# CH32F203VCT6-R0.net
KiCad netlist of a schematic drawn in Altium Designer
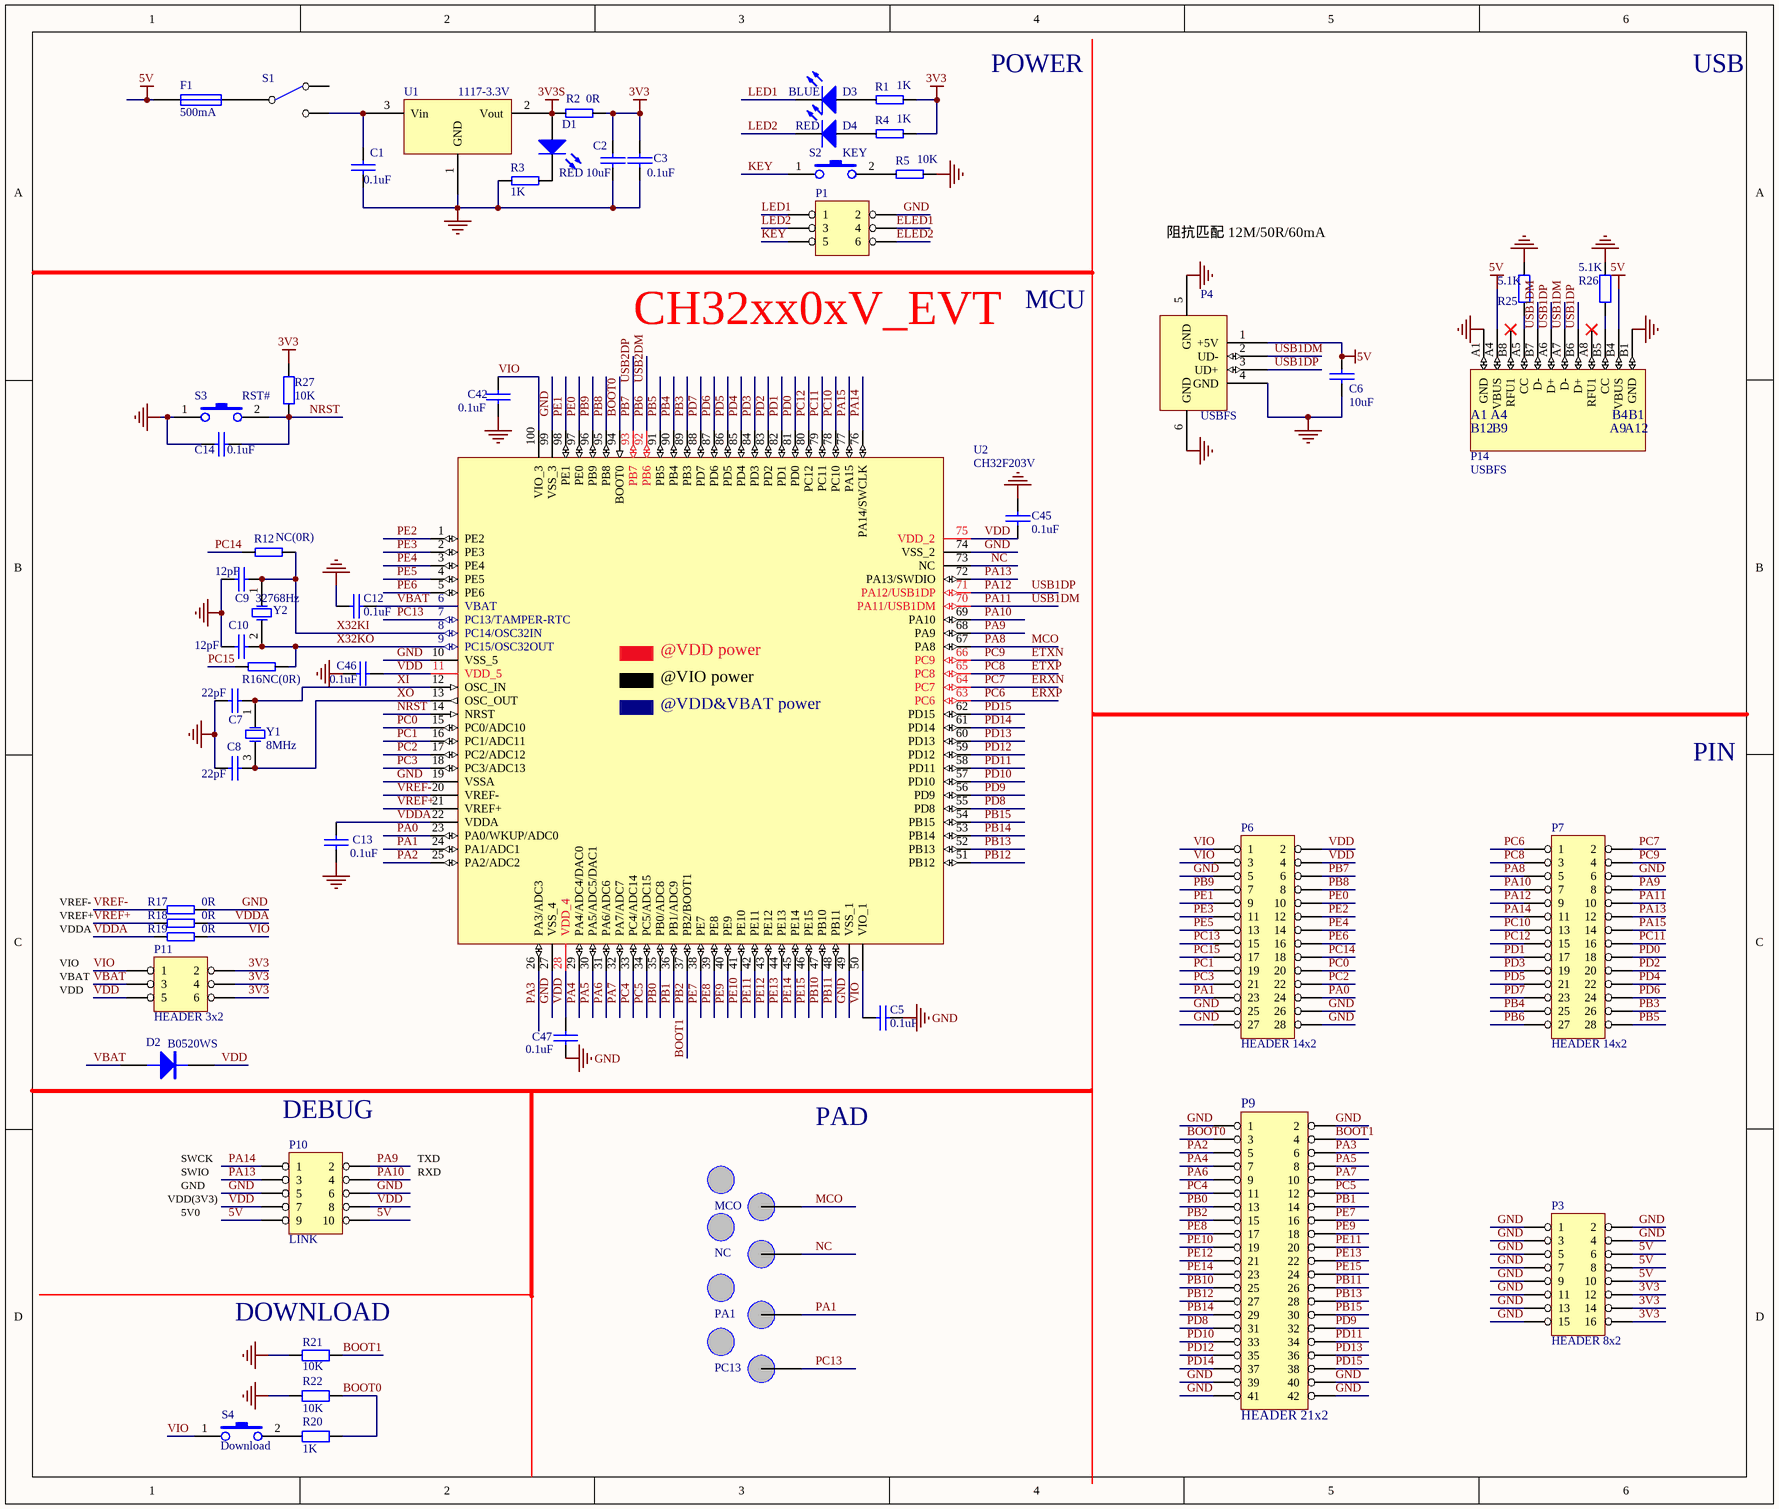
[diagram p0: CH32F203VCT6-R0.SchDoc]

(export (version "E")
  (design (tool "Eeschema 10.0.6"))
  (components
    (comp (ref "C1")
      (value "0.1uF")
      (footprint "0603_C")
      (description "Capacitor")
      (libsource (lib "*") (part "CAP"))
    )
    (comp (ref "C2")
      (value "10uF")
      (footprint "3216_C")
      (description "Capacitor")
      (libsource (lib "*") (part "CAP"))
    )
    (comp (ref "C3")
      (value "0.1uF")
      (footprint "0603_C")
      (description "Capacitor")
      (libsource (lib "*") (part "CAP"))
    )
    (comp (ref "C5")
      (value "0.1uF")
      (footprint "0603_C")
      (description "Capacitor")
      (libsource (lib "*") (part "CAP"))
    )
    (comp (ref "C6")
      (value "10uF")
      (footprint "3216_C")
      (description "Capacitor")
      (libsource (lib "") (part "CAP_1"))
    )
    (comp (ref "C7")
      (value "22pF")
      (footprint "0603_C")
      (description "Capacitor")
      (libsource (lib "*") (part "CAP"))
    )
    (comp (ref "C8")
      (value "22pF")
      (footprint "0603_C")
      (description "Capacitor")
      (libsource (lib "*") (part "CAP"))
    )
    (comp (ref "C9")
      (value "12pF")
      (footprint "0603_C")
      (description "Capacitor")
      (libsource (lib "*") (part "CAP"))
    )
    (comp (ref "C10")
      (value "12pF")
      (footprint "0603_C")
      (description "Capacitor")
      (libsource (lib "*") (part "CAP"))
    )
    (comp (ref "C12")
      (value "0.1uF")
      (footprint "0603_C")
      (description "Capacitor")
      (libsource (lib "*") (part "CAP"))
    )
    (comp (ref "C13")
      (value "0.1uF")
      (footprint "0603_C")
      (description "Capacitor")
      (libsource (lib "*") (part "CAP"))
    )
    (comp (ref "C14")
      (value "0.1uF")
      (footprint "0603_C")
      (description "Capacitor")
      (libsource (lib "") (part "CAP_1"))
    )
    (comp (ref "C42")
      (value "0.1uF")
      (footprint "0603_C")
      (description "Capacitor")
      (libsource (lib "*") (part "CAP"))
    )
    (comp (ref "C45")
      (value "0.1uF")
      (footprint "0603_C")
      (description "Capacitor")
      (libsource (lib "*") (part "CAP"))
    )
    (comp (ref "C46")
      (value "0.1uF")
      (footprint "0603_C")
      (description "Capacitor")
      (libsource (lib "*") (part "CAP"))
    )
    (comp (ref "C47")
      (value "0.1uF")
      (footprint "0603_C")
      (description "Capacitor")
      (libsource (lib "*") (part "CAP"))
    )
    (comp (ref "D1")
      (value "RED")
      (footprint "0603+")
      (description "Typical INFRARED GaAs LED")
      (fields (field (name "PUBLISHER") "Altium Limited"))
      (libsource (lib "*") (part "LED0"))
    )
    (comp (ref "D2")
      (value "B0520WS")
      (footprint "SOD-323")
      (description "Diode")
      (libsource (lib "*") (part "DIODE"))
    )
    (comp (ref "D3")
      (value "BLUE")
      (footprint "0603+")
      (description "Typical INFRARED GaAs LED")
      (fields (field (name "PUBLISHER") "Altium Limited"))
      (libsource (lib "*") (part "LED0"))
    )
    (comp (ref "D4")
      (value "RED")
      (footprint "0603+")
      (description "Typical INFRARED GaAs LED")
      (fields (field (name "PUBLISHER") "Altium Limited"))
      (libsource (lib "*") (part "LED0"))
    )
    (comp (ref "F1")
      (value "500mA")
      (footprint "0805")
      (description "Fuse")
      (libsource (lib "wch_sch_others") (part "FUSE1"))
    )
    (comp (ref "MCO")
      (value "Testpoint")
      (footprint "TESTPOINT1")
      (description "测试点")
      (libsource (lib "wch_sch_others") (part "Testpoint"))
    )
    (comp (ref "NC")
      (value "Testpoint")
      (footprint "TESTPOINT1")
      (description "测试点")
      (libsource (lib "wch_sch_others") (part "Testpoint"))
    )
    (comp (ref "P1")
      (value "IO")
      (footprint "MYPCB:IDC6-2.54mm")
      (description "Header, 3-Pin, Dual row")
      (libsource (lib "wch_sch_others") (part "HEADER 3x2"))
    )
    (comp (ref "P3")
      (value "HEADER 8x2")
      (footprint "MYPCB:IDC16-2.54mm")
      (description "Header, 8-Pin, Dual row")
      (libsource (lib "wch_sch_others") (part "HEADER 8x2"))
    )
    (comp (ref "P4")
      (value "USBFS")
      (footprint "USBAF")
      (description "USB Port")
      (libsource (lib "*") (part "USB"))
    )
    (comp (ref "P6")
      (value "HEADER 14x2")
      (footprint "MYPCB:IDC28-2.54MM")
      (description "Header, 14-Pin, Dual row")
      (libsource (lib "wch_sch_others") (part "HEADER 14x2"))
    )
    (comp (ref "P7")
      (value "HEADER 14x2")
      (footprint "MYPCB:IDC28-2.54MM")
      (description "Header, 14-Pin, Dual row")
      (libsource (lib "wch_sch_others") (part "HEADER 14x2"))
    )
    (comp (ref "P9")
      (value "HEADER 21x2")
      (footprint "MYPCB:IDC42-2.54MM")
      (description "Header, 21-Pin, Dual row")
      (libsource (lib "wch_sch_others") (part "HEADER 21x2"))
    )
    (comp (ref "P10")
      (value "LINK")
      (footprint "MYPCB:IDC10-2.54mm")
      (description "Header, 5-Pin, Dual row")
      (libsource (lib "wch_sch_others") (part "HEADER 5x2"))
    )
    (comp (ref "P11")
      (value "HEADER 3x2")
      (footprint "MYPCB:IDC6-2.54mm")
      (description "Header, 3-Pin, Dual row")
      (libsource (lib "wch_sch_others") (part "HEADER 3x2"))
    )
    (comp (ref "P14")
      (value "USBFS")
      (footprint "TYPE-C-Receptacle-2.0")
      (libsource (lib "*") (part "TYPE-C1"))
    )
    (comp (ref "PA1")
      (value "Testpoint")
      (footprint "TESTPOINT1")
      (description "测试点")
      (libsource (lib "wch_sch_others") (part "Testpoint"))
    )
    (comp (ref "PC13")
      (value "Testpoint")
      (footprint "TESTPOINT1")
      (description "测试点")
      (libsource (lib "wch_sch_others") (part "Testpoint"))
    )
    (comp (ref "R1") (value "1K") (footprint "0603") (libsource (lib "wch_sch_others") (part "RES")))
    (comp (ref "R2") (value "0R") (footprint "0603") (libsource (lib "wch_sch_others") (part "RES")))
    (comp (ref "R3") (value "1K") (footprint "0603") (libsource (lib "wch_sch_others") (part "RES")))
    (comp (ref "R4") (value "1K") (footprint "0603") (libsource (lib "wch_sch_others") (part "RES")))
    (comp (ref "R5") (value "10K") (footprint "0603") (libsource (lib "wch_sch_others") (part "RES")))
    (comp (ref "R12") (value "NC(0R)") (footprint "0603") (libsource (lib "wch_sch_others") (part "RES")))
    (comp (ref "R16") (value "NC(0R)") (footprint "0603") (libsource (lib "wch_sch_others") (part "RES")))
    (comp (ref "R17") (value "0R") (footprint "0603") (libsource (lib "*") (part "R")))
    (comp (ref "R18") (value "0R") (footprint "0603") (libsource (lib "*") (part "R")))
    (comp (ref "R19") (value "0R") (footprint "0603") (libsource (lib "*") (part "R")))
    (comp (ref "R20")
      (value "1K")
      (footprint "0603")
      (description "Resistor")
      (fields (field (name "PUBLISHER") "Altium Limited"))
      (libsource (lib "Miscellaneous Devices") (part "Res2"))
    )
    (comp (ref "R21")
      (value "10K")
      (footprint "0603")
      (description "Resistor")
      (fields (field (name "PUBLISHER") "Altium Limited"))
      (libsource (lib "Miscellaneous Devices") (part "Res2"))
    )
    (comp (ref "R22")
      (value "10K")
      (footprint "0603")
      (description "Resistor")
      (fields (field (name "PUBLISHER") "Altium Limited"))
      (libsource (lib "Miscellaneous Devices") (part "Res2"))
    )
    (comp (ref "R25")
      (value "5.1K")
      (footprint "0603")
      (description "Resistor")
      (libsource (lib "") (part "Res2_1"))
    )
    (comp (ref "R26")
      (value "5.1K")
      (footprint "0603")
      (description "Resistor")
      (libsource (lib "") (part "Res2_1"))
    )
    (comp (ref "R27")
      (value "10K")
      (footprint "0603")
      (description "Resistor")
      (fields (field (name "PUBLISHER") "Altium Limited"))
      (libsource (lib "") (part "Res2_1"))
    )
    (comp (ref "S1") (value "SW SPDT") (footprint "KEY2") (libsource (lib "*") (part "SW SPDT")))
    (comp (ref "S2")
      (value "KEY")
      (footprint "SMD_6.1x3.65x2.5mm-KEY")
      (libsource (lib "wch_sch_others") (part "KEY1"))
    )
    (comp (ref "S3")
      (value "RST#")
      (footprint "SMD_6.1x3.65x2.5mm-KEY")
      (libsource (lib "wch_sch_others") (part "KEY1"))
    )
    (comp (ref "S4")
      (value "Download")
      (footprint "SMD_6.1x3.65x2.5mm-KEY")
      (libsource (lib "wch_sch_others") (part "KEY1"))
    )
    (comp (ref "U1")
      (value "1117-3.3V")
      (footprint "SOT-223")
      (libsource (lib "wch_sch_others") (part "1117-3.3V"))
    )
    (comp (ref "U2")
      (value "CH32F203V")
      (footprint "LQFP100")
      (description "ARM M3 HD-MCU, 144MHz, 8*UART, 10*Timer, 4*OPA")
      (libsource (lib "CHXXX") (part "CH32F203V"))
    )
    (comp (ref "Y1")
      (value "8MHz")
      (footprint "XT3225")
      (description "Crystal Oscillator")
      (fields (field (name "PUBLISHER") "Altium Limited"))
      (libsource (lib "*") (part "XTAL"))
    )
    (comp (ref "Y2")
      (value "32768Hz")
      (footprint "FC-135")
      (description "Crystal Oscillator")
      (fields (field (name "PUBLISHER") "Altium Limited"))
      (libsource (lib "") (part "XTAL_1"))
    )
  )
  (nets
    (net (code "2") (name "/BOOT0") (class "Default")
      (node (ref "P9") (pin "3") (pinfunction "3_3") (pintype "passive"))
      (node (ref "R20") (pin "1") (pinfunction "1_1") (pintype "passive"))
      (node (ref "R22") (pin "1") (pinfunction "1_1") (pintype "passive"))
      (node (ref "U2") (pin "94") (pinfunction "BOOT0_94") (pintype "input"))
    )
    (net (code "3") (name "/BOOT1") (class "Default")
      (node (ref "P9") (pin "15") (pinfunction "15_15") (pintype "passive"))
      (node (ref "P9") (pin "4") (pinfunction "4_4") (pintype "passive"))
      (node (ref "R21") (pin "1") (pinfunction "1_1") (pintype "passive"))
      (node (ref "U2") (pin "37") (pinfunction "PB2/BOOT1_37") (pintype "bidirectional"))
    )
    (net (code "4") (name "/ELED1") (class "Default")
      (node (ref "P1") (pin "4") (pinfunction "4_4") (pintype "passive"))
    )
    (net (code "5") (name "/ELED2") (class "Default")
      (node (ref "P1") (pin "6") (pinfunction "6_6") (pintype "passive"))
    )
    (net (code "6") (name "/ERXN") (class "Default")
      (node (ref "P7") (pin "2") (pinfunction "2_2") (pintype "passive"))
      (node (ref "U2") (pin "64") (pinfunction "PC7_64") (pintype "bidirectional"))
    )
    (net (code "7") (name "/ERXP") (class "Default")
      (node (ref "P7") (pin "1") (pinfunction "1_1") (pintype "passive"))
      (node (ref "U2") (pin "63") (pinfunction "PC6_63") (pintype "bidirectional"))
    )
    (net (code "8") (name "/ETXN") (class "Default")
      (node (ref "P7") (pin "4") (pinfunction "4_4") (pintype "passive"))
      (node (ref "U2") (pin "66") (pinfunction "PC9_66") (pintype "bidirectional"))
    )
    (net (code "9") (name "/ETXP") (class "Default")
      (node (ref "P7") (pin "3") (pinfunction "3_3") (pintype "passive"))
      (node (ref "U2") (pin "65") (pinfunction "PC8_65") (pintype "bidirectional"))
    )
    (net (code "10") (name "/KEY") (class "Default")
      (node (ref "P1") (pin "5") (pinfunction "5_5") (pintype "passive"))
      (node (ref "S2") (pin "1") (pinfunction "1_1") (pintype "passive"))
    )
    (net (code "11") (name "/LED1") (class "Default")
      (node (ref "D3") (pin "2") (pinfunction "K_2") (pintype "passive"))
      (node (ref "P1") (pin "1") (pinfunction "1_1") (pintype "passive"))
    )
    (net (code "12") (name "/LED2") (class "Default")
      (node (ref "D4") (pin "2") (pinfunction "K_2") (pintype "passive"))
      (node (ref "P1") (pin "3") (pinfunction "3_3") (pintype "passive"))
    )
    (net (code "13") (name "/MCO") (class "Default")
      (node (ref "MCO") (pin "1") (pinfunction "point_1") (pintype "passive"))
      (node (ref "P7") (pin "5") (pinfunction "5_5") (pintype "passive"))
      (node (ref "U2") (pin "67") (pinfunction "PA8_67") (pintype "bidirectional"))
    )
    (net (code "14") (name "/NC") (class "Default")
      (node (ref "NC") (pin "1") (pinfunction "point_1") (pintype "passive"))
      (node (ref "U2") (pin "73") (pinfunction "NC_73") (pintype "tri_state"))
    )
    (net (code "15") (name "/NRST") (class "Default")
      (node (ref "C14") (pin "2") (pinfunction "2_2") (pintype "passive"))
      (node (ref "R27") (pin "1") (pinfunction "1_1") (pintype "passive"))
      (node (ref "S3") (pin "2") (pinfunction "2_2") (pintype "passive"))
      (node (ref "U2") (pin "14") (pinfunction "NRST_14") (pintype "input"))
    )
    (net (code "16") (name "/PA0") (class "Default")
      (node (ref "P6") (pin "24") (pinfunction "24_24") (pintype "passive"))
      (node (ref "U2") (pin "23") (pinfunction "PA0/WKUP/ADC0_23") (pintype "bidirectional"))
    )
    (net (code "17") (name "/PA1") (class "Default")
      (node (ref "P6") (pin "23") (pinfunction "23_23") (pintype "passive"))
      (node (ref "PA1") (pin "1") (pinfunction "point_1") (pintype "passive"))
      (node (ref "U2") (pin "24") (pinfunction "PA1/ADC1_24") (pintype "bidirectional"))
    )
    (net (code "18") (name "/PA2") (class "Default")
      (node (ref "P9") (pin "5") (pinfunction "5_5") (pintype "passive"))
      (node (ref "U2") (pin "25") (pinfunction "PA2/ADC2_25") (pintype "bidirectional"))
    )
    (net (code "19") (name "/PA3") (class "Default")
      (node (ref "P9") (pin "6") (pinfunction "6_6") (pintype "passive"))
      (node (ref "U2") (pin "26") (pinfunction "PA3/ADC3_26") (pintype "bidirectional"))
    )
    (net (code "20") (name "/PA4") (class "Default")
      (node (ref "P9") (pin "7") (pinfunction "7_7") (pintype "passive"))
      (node (ref "U2") (pin "29") (pinfunction "PA4/ADC4/DAC0_29") (pintype "bidirectional"))
    )
    (net (code "21") (name "/PA5") (class "Default")
      (node (ref "P9") (pin "8") (pinfunction "8_8") (pintype "passive"))
      (node (ref "U2") (pin "30") (pinfunction "PA5/ADC5/DAC1_30") (pintype "bidirectional"))
    )
    (net (code "22") (name "/PA6") (class "Default")
      (node (ref "P9") (pin "9") (pinfunction "9_9") (pintype "passive"))
      (node (ref "U2") (pin "31") (pinfunction "PA6/ADC6_31") (pintype "bidirectional"))
    )
    (net (code "23") (name "/PA7") (class "Default")
      (node (ref "P9") (pin "10") (pinfunction "10_10") (pintype "passive"))
      (node (ref "U2") (pin "32") (pinfunction "PA7/ADC7_32") (pintype "bidirectional"))
    )
    (net (code "24") (name "/PA9") (class "Default")
      (node (ref "P10") (pin "2") (pinfunction "2_2") (pintype "passive"))
      (node (ref "P7") (pin "8") (pinfunction "8_8") (pintype "passive"))
      (node (ref "U2") (pin "68") (pinfunction "PA9_68") (pintype "bidirectional"))
    )
    (net (code "25") (name "/PA10") (class "Default")
      (node (ref "P10") (pin "4") (pinfunction "4_4") (pintype "passive"))
      (node (ref "P7") (pin "7") (pinfunction "7_7") (pintype "passive"))
      (node (ref "U2") (pin "69") (pinfunction "PA10_69") (pintype "bidirectional"))
    )
    (net (code "26") (name "/PA11") (class "Default")
      (node (ref "P14") (pin "A7") (pinfunction "D-_A7") (pintype "bidirectional"))
      (node (ref "P14") (pin "B7") (pinfunction "D-_B7") (pintype "bidirectional"))
      (node (ref "P4") (pin "2") (pinfunction "UD-_2") (pintype "bidirectional"))
      (node (ref "P7") (pin "10") (pinfunction "10_10") (pintype "passive"))
      (node (ref "U2") (pin "70") (pinfunction "PA11/USB1DM_70") (pintype "bidirectional"))
    )
    (net (code "27") (name "/PA12") (class "Default")
      (node (ref "P14") (pin "A6") (pinfunction "D+_A6") (pintype "bidirectional"))
      (node (ref "P14") (pin "B6") (pinfunction "D+_B6") (pintype "bidirectional"))
      (node (ref "P4") (pin "3") (pinfunction "UD+_3") (pintype "bidirectional"))
      (node (ref "P7") (pin "9") (pinfunction "9_9") (pintype "passive"))
      (node (ref "U2") (pin "71") (pinfunction "PA12/USB1DP_71") (pintype "bidirectional"))
    )
    (net (code "28") (name "/PA13") (class "Default")
      (node (ref "P10") (pin "3") (pinfunction "3_3") (pintype "passive"))
      (node (ref "P7") (pin "12") (pinfunction "12_12") (pintype "passive"))
      (node (ref "U2") (pin "72") (pinfunction "PA13/SWDIO_72") (pintype "bidirectional"))
    )
    (net (code "29") (name "/PA14") (class "Default")
      (node (ref "P10") (pin "1") (pinfunction "1_1") (pintype "passive"))
      (node (ref "P7") (pin "11") (pinfunction "11_11") (pintype "passive"))
      (node (ref "U2") (pin "76") (pinfunction "PA14/SWCLK_76") (pintype "bidirectional"))
    )
    (net (code "30") (name "/PA15") (class "Default")
      (node (ref "P7") (pin "14") (pinfunction "14_14") (pintype "passive"))
      (node (ref "U2") (pin "77") (pinfunction "PA15_77") (pintype "bidirectional"))
    )
    (net (code "31") (name "/PB0") (class "Default")
      (node (ref "P9") (pin "13") (pinfunction "13_13") (pintype "passive"))
      (node (ref "U2") (pin "35") (pinfunction "PB0/ADC8_35") (pintype "bidirectional"))
    )
    (net (code "32") (name "/PB1") (class "Default")
      (node (ref "P9") (pin "14") (pinfunction "14_14") (pintype "passive"))
      (node (ref "U2") (pin "36") (pinfunction "PB1/ADC9_36") (pintype "bidirectional"))
    )
    (net (code "33") (name "/PB3") (class "Default")
      (node (ref "P7") (pin "26") (pinfunction "26_26") (pintype "passive"))
      (node (ref "U2") (pin "89") (pinfunction "PB3_89") (pintype "bidirectional"))
    )
    (net (code "34") (name "/PB4") (class "Default")
      (node (ref "P7") (pin "25") (pinfunction "25_25") (pintype "passive"))
      (node (ref "U2") (pin "90") (pinfunction "PB4_90") (pintype "bidirectional"))
    )
    (net (code "35") (name "/PB5") (class "Default")
      (node (ref "P7") (pin "28") (pinfunction "28_28") (pintype "passive"))
      (node (ref "U2") (pin "91") (pinfunction "PB5_91") (pintype "bidirectional"))
    )
    (net (code "36") (name "/PB6") (class "Default")
      (node (ref "P7") (pin "27") (pinfunction "27_27") (pintype "passive"))
      (node (ref "U2") (pin "92") (pinfunction "PB6_92") (pintype "bidirectional"))
    )
    (net (code "37") (name "/PB7") (class "Default")
      (node (ref "P6") (pin "6") (pinfunction "6_6") (pintype "passive"))
      (node (ref "U2") (pin "93") (pinfunction "PB7_93") (pintype "bidirectional"))
    )
    (net (code "38") (name "/PB8") (class "Default")
      (node (ref "P6") (pin "8") (pinfunction "8_8") (pintype "passive"))
      (node (ref "U2") (pin "95") (pinfunction "PB8_95") (pintype "bidirectional"))
    )
    (net (code "39") (name "/PB9") (class "Default")
      (node (ref "P6") (pin "7") (pinfunction "7_7") (pintype "passive"))
      (node (ref "U2") (pin "96") (pinfunction "PB9_96") (pintype "bidirectional"))
    )
    (net (code "40") (name "/PB10") (class "Default")
      (node (ref "P9") (pin "25") (pinfunction "25_25") (pintype "passive"))
      (node (ref "U2") (pin "47") (pinfunction "PB10_47") (pintype "bidirectional"))
    )
    (net (code "41") (name "/PB11") (class "Default")
      (node (ref "P9") (pin "26") (pinfunction "26_26") (pintype "passive"))
      (node (ref "U2") (pin "48") (pinfunction "PB11_48") (pintype "bidirectional"))
    )
    (net (code "42") (name "/PB12") (class "Default")
      (node (ref "P9") (pin "27") (pinfunction "27_27") (pintype "passive"))
      (node (ref "U2") (pin "51") (pinfunction "PB12_51") (pintype "bidirectional"))
    )
    (net (code "43") (name "/PB13") (class "Default")
      (node (ref "P9") (pin "28") (pinfunction "28_28") (pintype "passive"))
      (node (ref "U2") (pin "52") (pinfunction "PB13_52") (pintype "bidirectional"))
    )
    (net (code "44") (name "/PB14") (class "Default")
      (node (ref "P9") (pin "29") (pinfunction "29_29") (pintype "passive"))
      (node (ref "U2") (pin "53") (pinfunction "PB14_53") (pintype "bidirectional"))
    )
    (net (code "45") (name "/PB15") (class "Default")
      (node (ref "P9") (pin "30") (pinfunction "30_30") (pintype "passive"))
      (node (ref "U2") (pin "54") (pinfunction "PB15_54") (pintype "bidirectional"))
    )
    (net (code "46") (name "/PC0") (class "Default")
      (node (ref "P6") (pin "20") (pinfunction "20_20") (pintype "passive"))
      (node (ref "U2") (pin "15") (pinfunction "PC0/ADC10_15") (pintype "bidirectional"))
    )
    (net (code "47") (name "/PC1") (class "Default")
      (node (ref "P6") (pin "19") (pinfunction "19_19") (pintype "passive"))
      (node (ref "U2") (pin "16") (pinfunction "PC1/ADC11_16") (pintype "bidirectional"))
    )
    (net (code "48") (name "/PC2") (class "Default")
      (node (ref "P6") (pin "22") (pinfunction "22_22") (pintype "passive"))
      (node (ref "U2") (pin "17") (pinfunction "PC2/ADC12_17") (pintype "bidirectional"))
    )
    (net (code "49") (name "/PC3") (class "Default")
      (node (ref "P6") (pin "21") (pinfunction "21_21") (pintype "passive"))
      (node (ref "U2") (pin "18") (pinfunction "PC3/ADC13_18") (pintype "bidirectional"))
    )
    (net (code "50") (name "/PC4") (class "Default")
      (node (ref "P9") (pin "11") (pinfunction "11_11") (pintype "passive"))
      (node (ref "U2") (pin "33") (pinfunction "PC4/ADC14_33") (pintype "bidirectional"))
    )
    (net (code "51") (name "/PC5") (class "Default")
      (node (ref "P9") (pin "12") (pinfunction "12_12") (pintype "passive"))
      (node (ref "U2") (pin "34") (pinfunction "PC5/ADC15_34") (pintype "bidirectional"))
    )
    (net (code "52") (name "/PC10") (class "Default")
      (node (ref "P7") (pin "13") (pinfunction "13_13") (pintype "passive"))
      (node (ref "U2") (pin "78") (pinfunction "PC10_78") (pintype "bidirectional"))
    )
    (net (code "53") (name "/PC11") (class "Default")
      (node (ref "P7") (pin "16") (pinfunction "16_16") (pintype "passive"))
      (node (ref "U2") (pin "79") (pinfunction "PC11_79") (pintype "bidirectional"))
    )
    (net (code "54") (name "/PC12") (class "Default")
      (node (ref "P7") (pin "15") (pinfunction "15_15") (pintype "passive"))
      (node (ref "U2") (pin "80") (pinfunction "PC12_80") (pintype "bidirectional"))
    )
    (net (code "55") (name "/PC13") (class "Default")
      (node (ref "P6") (pin "15") (pinfunction "15_15") (pintype "passive"))
      (node (ref "PC13") (pin "1") (pinfunction "point_1") (pintype "passive"))
      (node (ref "U2") (pin "7") (pinfunction "PC13/TAMPER-RTC_7") (pintype "bidirectional"))
    )
    (net (code "56") (name "/PC14") (class "Default")
      (node (ref "P6") (pin "18") (pinfunction "18_18") (pintype "passive"))
      (node (ref "R12") (pin "1") (pintype "passive"))
    )
    (net (code "57") (name "/PC15") (class "Default")
      (node (ref "P6") (pin "17") (pinfunction "17_17") (pintype "passive"))
      (node (ref "R16") (pin "1") (pintype "passive"))
    )
    (net (code "58") (name "/PD0") (class "Default")
      (node (ref "P7") (pin "18") (pinfunction "18_18") (pintype "passive"))
      (node (ref "U2") (pin "81") (pinfunction "PD0_81") (pintype "bidirectional"))
    )
    (net (code "59") (name "/PD1") (class "Default")
      (node (ref "P7") (pin "17") (pinfunction "17_17") (pintype "passive"))
      (node (ref "U2") (pin "82") (pinfunction "PD1_82") (pintype "bidirectional"))
    )
    (net (code "60") (name "/PD2") (class "Default")
      (node (ref "P7") (pin "20") (pinfunction "20_20") (pintype "passive"))
      (node (ref "U2") (pin "83") (pinfunction "PD2_83") (pintype "bidirectional"))
    )
    (net (code "61") (name "/PD3") (class "Default")
      (node (ref "P7") (pin "19") (pinfunction "19_19") (pintype "passive"))
      (node (ref "U2") (pin "84") (pinfunction "PD3_84") (pintype "bidirectional"))
    )
    (net (code "62") (name "/PD4") (class "Default")
      (node (ref "P7") (pin "22") (pinfunction "22_22") (pintype "passive"))
      (node (ref "U2") (pin "85") (pinfunction "PD4_85") (pintype "bidirectional"))
    )
    (net (code "63") (name "/PD5") (class "Default")
      (node (ref "P7") (pin "21") (pinfunction "21_21") (pintype "passive"))
      (node (ref "U2") (pin "86") (pinfunction "PD5_86") (pintype "bidirectional"))
    )
    (net (code "64") (name "/PD6") (class "Default")
      (node (ref "P7") (pin "24") (pinfunction "24_24") (pintype "passive"))
      (node (ref "U2") (pin "87") (pinfunction "PD6_87") (pintype "bidirectional"))
    )
    (net (code "65") (name "/PD7") (class "Default")
      (node (ref "P7") (pin "23") (pinfunction "23_23") (pintype "passive"))
      (node (ref "U2") (pin "88") (pinfunction "PD7_88") (pintype "bidirectional"))
    )
    (net (code "66") (name "/PD8") (class "Default")
      (node (ref "P9") (pin "31") (pinfunction "31_31") (pintype "passive"))
      (node (ref "U2") (pin "55") (pinfunction "PD8_55") (pintype "bidirectional"))
    )
    (net (code "67") (name "/PD9") (class "Default")
      (node (ref "P9") (pin "32") (pinfunction "32_32") (pintype "passive"))
      (node (ref "U2") (pin "56") (pinfunction "PD9_56") (pintype "bidirectional"))
    )
    (net (code "68") (name "/PD10") (class "Default")
      (node (ref "P9") (pin "33") (pinfunction "33_33") (pintype "passive"))
      (node (ref "U2") (pin "57") (pinfunction "PD10_57") (pintype "bidirectional"))
    )
    (net (code "69") (name "/PD11") (class "Default")
      (node (ref "P9") (pin "34") (pinfunction "34_34") (pintype "passive"))
      (node (ref "U2") (pin "58") (pinfunction "PD11_58") (pintype "bidirectional"))
    )
    (net (code "70") (name "/PD12") (class "Default")
      (node (ref "P9") (pin "35") (pinfunction "35_35") (pintype "passive"))
      (node (ref "U2") (pin "59") (pinfunction "PD12_59") (pintype "bidirectional"))
    )
    (net (code "71") (name "/PD13") (class "Default")
      (node (ref "P9") (pin "36") (pinfunction "36_36") (pintype "passive"))
      (node (ref "U2") (pin "60") (pinfunction "PD13_60") (pintype "bidirectional"))
    )
    (net (code "72") (name "/PD14") (class "Default")
      (node (ref "P9") (pin "37") (pinfunction "37_37") (pintype "passive"))
      (node (ref "U2") (pin "61") (pinfunction "PD14_61") (pintype "bidirectional"))
    )
    (net (code "73") (name "/PD15") (class "Default")
      (node (ref "P9") (pin "38") (pinfunction "38_38") (pintype "passive"))
      (node (ref "U2") (pin "62") (pinfunction "PD15_62") (pintype "bidirectional"))
    )
    (net (code "74") (name "/PE0") (class "Default")
      (node (ref "P6") (pin "10") (pinfunction "10_10") (pintype "passive"))
      (node (ref "U2") (pin "97") (pinfunction "PE0_97") (pintype "bidirectional"))
    )
    (net (code "75") (name "/PE1") (class "Default")
      (node (ref "P6") (pin "9") (pinfunction "9_9") (pintype "passive"))
      (node (ref "U2") (pin "98") (pinfunction "PE1_98") (pintype "bidirectional"))
    )
    (net (code "76") (name "/PE2") (class "Default")
      (node (ref "P6") (pin "12") (pinfunction "12_12") (pintype "passive"))
      (node (ref "U2") (pin "1") (pinfunction "PE2_1") (pintype "bidirectional"))
    )
    (net (code "77") (name "/PE3") (class "Default")
      (node (ref "P6") (pin "11") (pinfunction "11_11") (pintype "passive"))
      (node (ref "U2") (pin "2") (pinfunction "PE3_2") (pintype "bidirectional"))
    )
    (net (code "78") (name "/PE4") (class "Default")
      (node (ref "P6") (pin "14") (pinfunction "14_14") (pintype "passive"))
      (node (ref "U2") (pin "3") (pinfunction "PE4_3") (pintype "bidirectional"))
    )
    (net (code "79") (name "/PE5") (class "Default")
      (node (ref "P6") (pin "13") (pinfunction "13_13") (pintype "passive"))
      (node (ref "U2") (pin "4") (pinfunction "PE5_4") (pintype "bidirectional"))
    )
    (net (code "80") (name "/PE6") (class "Default")
      (node (ref "P6") (pin "16") (pinfunction "16_16") (pintype "passive"))
      (node (ref "U2") (pin "5") (pinfunction "PE6_5") (pintype "bidirectional"))
    )
    (net (code "81") (name "/PE7") (class "Default")
      (node (ref "P9") (pin "16") (pinfunction "16_16") (pintype "passive"))
      (node (ref "U2") (pin "38") (pinfunction "PE7_38") (pintype "bidirectional"))
    )
    (net (code "82") (name "/PE8") (class "Default")
      (node (ref "P9") (pin "17") (pinfunction "17_17") (pintype "passive"))
      (node (ref "U2") (pin "39") (pinfunction "PE8_39") (pintype "bidirectional"))
    )
    (net (code "83") (name "/PE9") (class "Default")
      (node (ref "P9") (pin "18") (pinfunction "18_18") (pintype "passive"))
      (node (ref "U2") (pin "40") (pinfunction "PE9_40") (pintype "bidirectional"))
    )
    (net (code "84") (name "/PE10") (class "Default")
      (node (ref "P9") (pin "19") (pinfunction "19_19") (pintype "passive"))
      (node (ref "U2") (pin "41") (pinfunction "PE10_41") (pintype "bidirectional"))
    )
    (net (code "85") (name "/PE11") (class "Default")
      (node (ref "P9") (pin "20") (pinfunction "20_20") (pintype "passive"))
      (node (ref "U2") (pin "42") (pinfunction "PE11_42") (pintype "bidirectional"))
    )
    (net (code "86") (name "/PE12") (class "Default")
      (node (ref "P9") (pin "21") (pinfunction "21_21") (pintype "passive"))
      (node (ref "U2") (pin "43") (pinfunction "PE12_43") (pintype "bidirectional"))
    )
    (net (code "87") (name "/PE13") (class "Default")
      (node (ref "P9") (pin "22") (pinfunction "22_22") (pintype "passive"))
      (node (ref "U2") (pin "44") (pinfunction "PE13_44") (pintype "bidirectional"))
    )
    (net (code "88") (name "/PE14") (class "Default")
      (node (ref "P9") (pin "23") (pinfunction "23_23") (pintype "passive"))
      (node (ref "U2") (pin "45") (pinfunction "PE14_45") (pintype "bidirectional"))
    )
    (net (code "89") (name "/PE15") (class "Default")
      (node (ref "P9") (pin "24") (pinfunction "24_24") (pintype "passive"))
      (node (ref "U2") (pin "46") (pinfunction "PE15_46") (pintype "bidirectional"))
    )
    (net (code "90") (name "/VBAT") (class "Default")
      (node (ref "C12") (pin "2") (pinfunction "2_2") (pintype "passive"))
      (node (ref "D2") (pin "1") (pinfunction "A_1") (pintype "passive"))
      (node (ref "P11") (pin "3") (pinfunction "3_3") (pintype "passive"))
      (node (ref "U2") (pin "6") (pinfunction "VBAT_6") (pintype "power_in"))
    )
    (net (code "91") (name "/VDD") (class "Default")
      (node (ref "C45") (pin "1") (pinfunction "1_1") (pintype "passive"))
      (node (ref "C46") (pin "1") (pinfunction "1_1") (pintype "passive"))
      (node (ref "C47") (pin "2") (pinfunction "2_2") (pintype "passive"))
      (node (ref "D2") (pin "2") (pinfunction "K_2") (pintype "passive"))
      (node (ref "P10") (pin "7") (pinfunction "7_7") (pintype "passive"))
      (node (ref "P10") (pin "8") (pinfunction "8_8") (pintype "passive"))
      (node (ref "P11") (pin "5") (pinfunction "5_5") (pintype "passive"))
      (node (ref "P6") (pin "2") (pinfunction "2_2") (pintype "passive"))
      (node (ref "P6") (pin "4") (pinfunction "4_4") (pintype "passive"))
      (node (ref "U2") (pin "11") (pinfunction "VDD_5_11") (pintype "power_in"))
      (node (ref "U2") (pin "28") (pinfunction "VDD_4_28") (pintype "power_in"))
      (node (ref "U2") (pin "75") (pinfunction "VDD_2_75") (pintype "power_in"))
    )
    (net (code "92") (name "/VDDA") (class "Default")
      (node (ref "C13") (pin "1") (pinfunction "1_1") (pintype "passive"))
      (node (ref "R18") (pin "1") (pinfunction "1_1") (pintype "passive"))
      (node (ref "R19") (pin "2") (pinfunction "2_2") (pintype "passive"))
      (node (ref "U2") (pin "22") (pinfunction "VDDA_22") (pintype "power_in"))
    )
    (net (code "93") (name "/VIO") (class "Default")
      (node (ref "C42") (pin "2") (pinfunction "2_2") (pintype "passive"))
      (node (ref "C5") (pin "1") (pinfunction "1_1") (pintype "passive"))
      (node (ref "P11") (pin "1") (pinfunction "1_1") (pintype "passive"))
      (node (ref "P6") (pin "1") (pinfunction "1_1") (pintype "passive"))
      (node (ref "P6") (pin "3") (pinfunction "3_3") (pintype "passive"))
      (node (ref "R19") (pin "1") (pinfunction "1_1") (pintype "passive"))
      (node (ref "S4") (pin "1") (pinfunction "1_1") (pintype "passive"))
      (node (ref "U2") (pin "100") (pinfunction "VIO_3_100") (pintype "power_in"))
      (node (ref "U2") (pin "50") (pinfunction "VIO_1_50") (pintype "power_in"))
    )
    (net (code "94") (name "/VREF+") (class "Default")
      (node (ref "R18") (pin "2") (pinfunction "2_2") (pintype "passive"))
      (node (ref "U2") (pin "21") (pinfunction "VREF+_21") (pintype "power_in"))
    )
    (net (code "95") (name "/VREF-") (class "Default")
      (node (ref "R17") (pin "2") (pinfunction "2_2") (pintype "passive"))
      (node (ref "U2") (pin "20") (pinfunction "VREF-_20") (pintype "power_in"))
    )
    (net (code "96") (name "/X32KI") (class "Default")
      (node (ref "C9") (pin "2") (pinfunction "2_2") (pintype "passive"))
      (node (ref "R12") (pin "2") (pintype "passive"))
      (node (ref "U2") (pin "8") (pinfunction "PC14/OSC32IN_8") (pintype "bidirectional"))
      (node (ref "Y2") (pin "1") (pinfunction "OSC1_1") (pintype "passive"))
    )
    (net (code "97") (name "/X32KO") (class "Default")
      (node (ref "C10") (pin "2") (pinfunction "2_2") (pintype "passive"))
      (node (ref "R16") (pin "2") (pintype "passive"))
      (node (ref "U2") (pin "9") (pinfunction "PC15/OSC32OUT_9") (pintype "bidirectional"))
      (node (ref "Y2") (pin "2") (pinfunction "OSC2_2") (pintype "passive"))
    )
    (net (code "98") (name "/XI") (class "Default")
      (node (ref "C7") (pin "2") (pinfunction "2_2") (pintype "passive"))
      (node (ref "U2") (pin "12") (pinfunction "OSC_IN_12") (pintype "input"))
      (node (ref "Y1") (pin "1") (pinfunction "OSC1_1") (pintype "passive"))
    )
    (net (code "99") (name "/XO") (class "Default")
      (node (ref "C8") (pin "2") (pinfunction "2_2") (pintype "passive"))
      (node (ref "U2") (pin "13") (pinfunction "OSC_OUT_13") (pintype "output"))
      (node (ref "Y1") (pin "3") (pinfunction "OSC2_3") (pintype "passive"))
    )
    (net (code "100") (name "3V3") (class "Default")
      (node (ref "C2") (pin "1") (pinfunction "1_1") (pintype "passive"))
      (node (ref "C3") (pin "1") (pinfunction "1_1") (pintype "passive"))
      (node (ref "P11") (pin "2") (pinfunction "2_2") (pintype "passive"))
      (node (ref "P11") (pin "4") (pinfunction "4_4") (pintype "passive"))
      (node (ref "P11") (pin "6") (pinfunction "6_6") (pintype "passive"))
      (node (ref "P3") (pin "12") (pinfunction "12_12") (pintype "passive"))
      (node (ref "P3") (pin "14") (pinfunction "14_14") (pintype "passive"))
      (node (ref "P3") (pin "16") (pinfunction "16_16") (pintype "passive"))
      (node (ref "R1") (pin "1") (pintype "passive"))
      (node (ref "R2") (pin "1") (pintype "passive"))
      (node (ref "R27") (pin "2") (pinfunction "2_2") (pintype "passive"))
      (node (ref "R4") (pin "1") (pintype "passive"))
    )
    (net (code "101") (name "3V3S") (class "Default")
      (node (ref "D1") (pin "1") (pinfunction "A_1") (pintype "passive"))
      (node (ref "R2") (pin "2") (pintype "passive"))
      (node (ref "U1") (pin "2") (pinfunction "Vout_2") (pintype "passive"))
    )
    (net (code "102") (name "5V") (class "Default")
      (node (ref "C6") (pin "1") (pinfunction "1_1") (pintype "passive"))
      (node (ref "F1") (pin "1") (pinfunction "1_1") (pintype "passive"))
      (node (ref "P10") (pin "10") (pinfunction "10_10") (pintype "passive"))
      (node (ref "P10") (pin "9") (pinfunction "9_9") (pintype "passive"))
      (node (ref "P14") (pin "A4") (pinfunction "VBUS_A4") (pintype "bidirectional"))
      (node (ref "P14") (pin "B4") (pinfunction "VBUS_B4") (pintype "bidirectional"))
      (node (ref "P3") (pin "10") (pinfunction "10_10") (pintype "passive"))
      (node (ref "P3") (pin "6") (pinfunction "6_6") (pintype "passive"))
      (node (ref "P3") (pin "8") (pinfunction "8_8") (pintype "passive"))
      (node (ref "P4") (pin "1") (pinfunction "+5V_1") (pintype "power_in"))
    )
    (net (code "103") (name "GND") (class "Default")
      (node (ref "C1") (pin "2") (pinfunction "2_2") (pintype "passive"))
      (node (ref "C10") (pin "1") (pinfunction "1_1") (pintype "passive"))
      (node (ref "C12") (pin "1") (pinfunction "1_1") (pintype "passive"))
      (node (ref "C13") (pin "2") (pinfunction "2_2") (pintype "passive"))
      (node (ref "C14") (pin "1") (pinfunction "1_1") (pintype "passive"))
      (node (ref "C2") (pin "2") (pinfunction "2_2") (pintype "passive"))
      (node (ref "C3") (pin "2") (pinfunction "2_2") (pintype "passive"))
      (node (ref "C42") (pin "1") (pinfunction "1_1") (pintype "passive"))
      (node (ref "C45") (pin "2") (pinfunction "2_2") (pintype "passive"))
      (node (ref "C46") (pin "2") (pinfunction "2_2") (pintype "passive"))
      (node (ref "C47") (pin "1") (pinfunction "1_1") (pintype "passive"))
      (node (ref "C5") (pin "2") (pinfunction "2_2") (pintype "passive"))
      (node (ref "C6") (pin "2") (pinfunction "2_2") (pintype "passive"))
      (node (ref "C7") (pin "1") (pinfunction "1_1") (pintype "passive"))
      (node (ref "C8") (pin "1") (pinfunction "1_1") (pintype "passive"))
      (node (ref "C9") (pin "1") (pinfunction "1_1") (pintype "passive"))
      (node (ref "P1") (pin "2") (pinfunction "2_2") (pintype "passive"))
      (node (ref "P10") (pin "5") (pinfunction "5_5") (pintype "passive"))
      (node (ref "P10") (pin "6") (pinfunction "6_6") (pintype "passive"))
      (node (ref "P14") (pin "A1") (pinfunction "GND_A1") (pintype "bidirectional"))
      (node (ref "P14") (pin "B1") (pinfunction "GND_B1") (pintype "bidirectional"))
      (node (ref "P3") (pin "1") (pinfunction "1_1") (pintype "passive"))
      (node (ref "P3") (pin "11") (pinfunction "11_11") (pintype "passive"))
      (node (ref "P3") (pin "13") (pinfunction "13_13") (pintype "passive"))
      (node (ref "P3") (pin "15") (pinfunction "15_15") (pintype "passive"))
      (node (ref "P3") (pin "2") (pinfunction "2_2") (pintype "passive"))
      (node (ref "P3") (pin "3") (pinfunction "3_3") (pintype "passive"))
      (node (ref "P3") (pin "4") (pinfunction "4_4") (pintype "passive"))
      (node (ref "P3") (pin "5") (pinfunction "5_5") (pintype "passive"))
      (node (ref "P3") (pin "7") (pinfunction "7_7") (pintype "passive"))
      (node (ref "P3") (pin "9") (pinfunction "9_9") (pintype "passive"))
      (node (ref "P4") (pin "4") (pinfunction "GND_4") (pintype "power_in"))
      (node (ref "P4") (pin "5") (pinfunction "GND_5") (pintype "power_in"))
      (node (ref "P4") (pin "6") (pinfunction "GND_6") (pintype "power_in"))
      (node (ref "P6") (pin "25") (pinfunction "25_25") (pintype "passive"))
      (node (ref "P6") (pin "26") (pinfunction "26_26") (pintype "passive"))
      (node (ref "P6") (pin "27") (pinfunction "27_27") (pintype "passive"))
      (node (ref "P6") (pin "28") (pinfunction "28_28") (pintype "passive"))
      (node (ref "P6") (pin "5") (pinfunction "5_5") (pintype "passive"))
      (node (ref "P7") (pin "6") (pinfunction "6_6") (pintype "passive"))
      (node (ref "P9") (pin "1") (pinfunction "1_1") (pintype "passive"))
      (node (ref "P9") (pin "2") (pinfunction "2_2") (pintype "passive"))
      (node (ref "P9") (pin "39") (pinfunction "39_39") (pintype "passive"))
      (node (ref "P9") (pin "40") (pinfunction "40_40") (pintype "passive"))
      (node (ref "P9") (pin "41") (pinfunction "41_41") (pintype "passive"))
      (node (ref "P9") (pin "42") (pinfunction "42_42") (pintype "passive"))
      (node (ref "R17") (pin "1") (pinfunction "1_1") (pintype "passive"))
      (node (ref "R21") (pin "2") (pinfunction "2_2") (pintype "passive"))
      (node (ref "R22") (pin "2") (pinfunction "2_2") (pintype "passive"))
      (node (ref "R25") (pin "2") (pinfunction "2_2") (pintype "passive"))
      (node (ref "R26") (pin "2") (pinfunction "2_2") (pintype "passive"))
      (node (ref "R3") (pin "2") (pintype "passive"))
      (node (ref "R5") (pin "1") (pintype "passive"))
      (node (ref "S3") (pin "1") (pinfunction "1_1") (pintype "passive"))
      (node (ref "U1") (pin "1") (pinfunction "GND_1") (pintype "passive"))
      (node (ref "U2") (pin "10") (pinfunction "VSS_5_10") (pintype "power_in"))
      (node (ref "U2") (pin "19") (pinfunction "VSSA_19") (pintype "power_in"))
      (node (ref "U2") (pin "27") (pinfunction "VSS_4_27") (pintype "power_in"))
      (node (ref "U2") (pin "49") (pinfunction "VSS_1_49") (pintype "power_in"))
      (node (ref "U2") (pin "74") (pinfunction "VSS_2_74") (pintype "power_in"))
      (node (ref "U2") (pin "99") (pinfunction "VSS_3_99") (pintype "power_in"))
    )
    (net (code "104") (name "Net-(D1-K)") (class "Default")
      (node (ref "D1") (pin "2") (pinfunction "K_2") (pintype "passive"))
      (node (ref "R3") (pin "1") (pintype "passive"))
    )
    (net (code "105") (name "Net-(D3-A)") (class "Default")
      (node (ref "D3") (pin "1") (pinfunction "A_1") (pintype "passive"))
      (node (ref "R1") (pin "2") (pintype "passive"))
    )
    (net (code "106") (name "Net-(D4-A)") (class "Default")
      (node (ref "D4") (pin "1") (pinfunction "A_1") (pintype "passive"))
      (node (ref "R4") (pin "2") (pintype "passive"))
    )
    (net (code "107") (name "Net-(P14-CC-PadA5)") (class "Default")
      (node (ref "P14") (pin "A5") (pinfunction "CC_A5") (pintype "bidirectional"))
      (node (ref "R25") (pin "1") (pinfunction "1_1") (pintype "passive"))
    )
    (net (code "108") (name "Net-(P14-CC-PadB5)") (class "Default")
      (node (ref "P14") (pin "B5") (pinfunction "CC_B5") (pintype "bidirectional"))
      (node (ref "R26") (pin "1") (pinfunction "1_1") (pintype "passive"))
    )
    (net (code "109") (name "Net-(R5-Pad2)") (class "Default")
      (node (ref "R5") (pin "2") (pintype "passive"))
      (node (ref "S2") (pin "2") (pinfunction "2_2") (pintype "passive"))
    )
    (net (code "110") (name "Net-(R20-Pad2)") (class "Default")
      (node (ref "R20") (pin "2") (pinfunction "2_2") (pintype "passive"))
      (node (ref "S4") (pin "2") (pinfunction "2_2") (pintype "passive"))
    )
    (net (code "111") (name "Net-(S1-COMMON)") (class "Default")
      (node (ref "F1") (pin "2") (pinfunction "2_2") (pintype "passive"))
      (node (ref "S1") (pin "1") (pinfunction "COMMON_1") (pintype "passive"))
    )
    (net (code "112") (name "Net-(S1-NC)") (class "Default")
      (node (ref "C1") (pin "1") (pinfunction "1_1") (pintype "passive"))
      (node (ref "S1") (pin "2") (pinfunction "NC_2") (pintype "passive"))
      (node (ref "U1") (pin "3") (pinfunction "Vin_3") (pintype "passive"))
    )
    (net (code "113") (name "unconnected-(P14-RFU1-PadA8)") (class "Default")
      (node (ref "P14") (pin "A8") (pinfunction "RFU1_A8") (pintype "bidirectional+no_connect"))
    )
    (net (code "114") (name "unconnected-(P14-RFU1-PadB8)") (class "Default")
      (node (ref "P14") (pin "B8") (pinfunction "RFU1_B8") (pintype "bidirectional+no_connect"))
    )
    (net (code "115") (name "unconnected-(S1-NO-Pad3)") (class "Default")
      (node (ref "S1") (pin "3") (pinfunction "NO_3") (pintype "passive"))
    )
  )
)
